# CPU_Power.net
KiCad netlist of a schematic drawn in Altium Designer
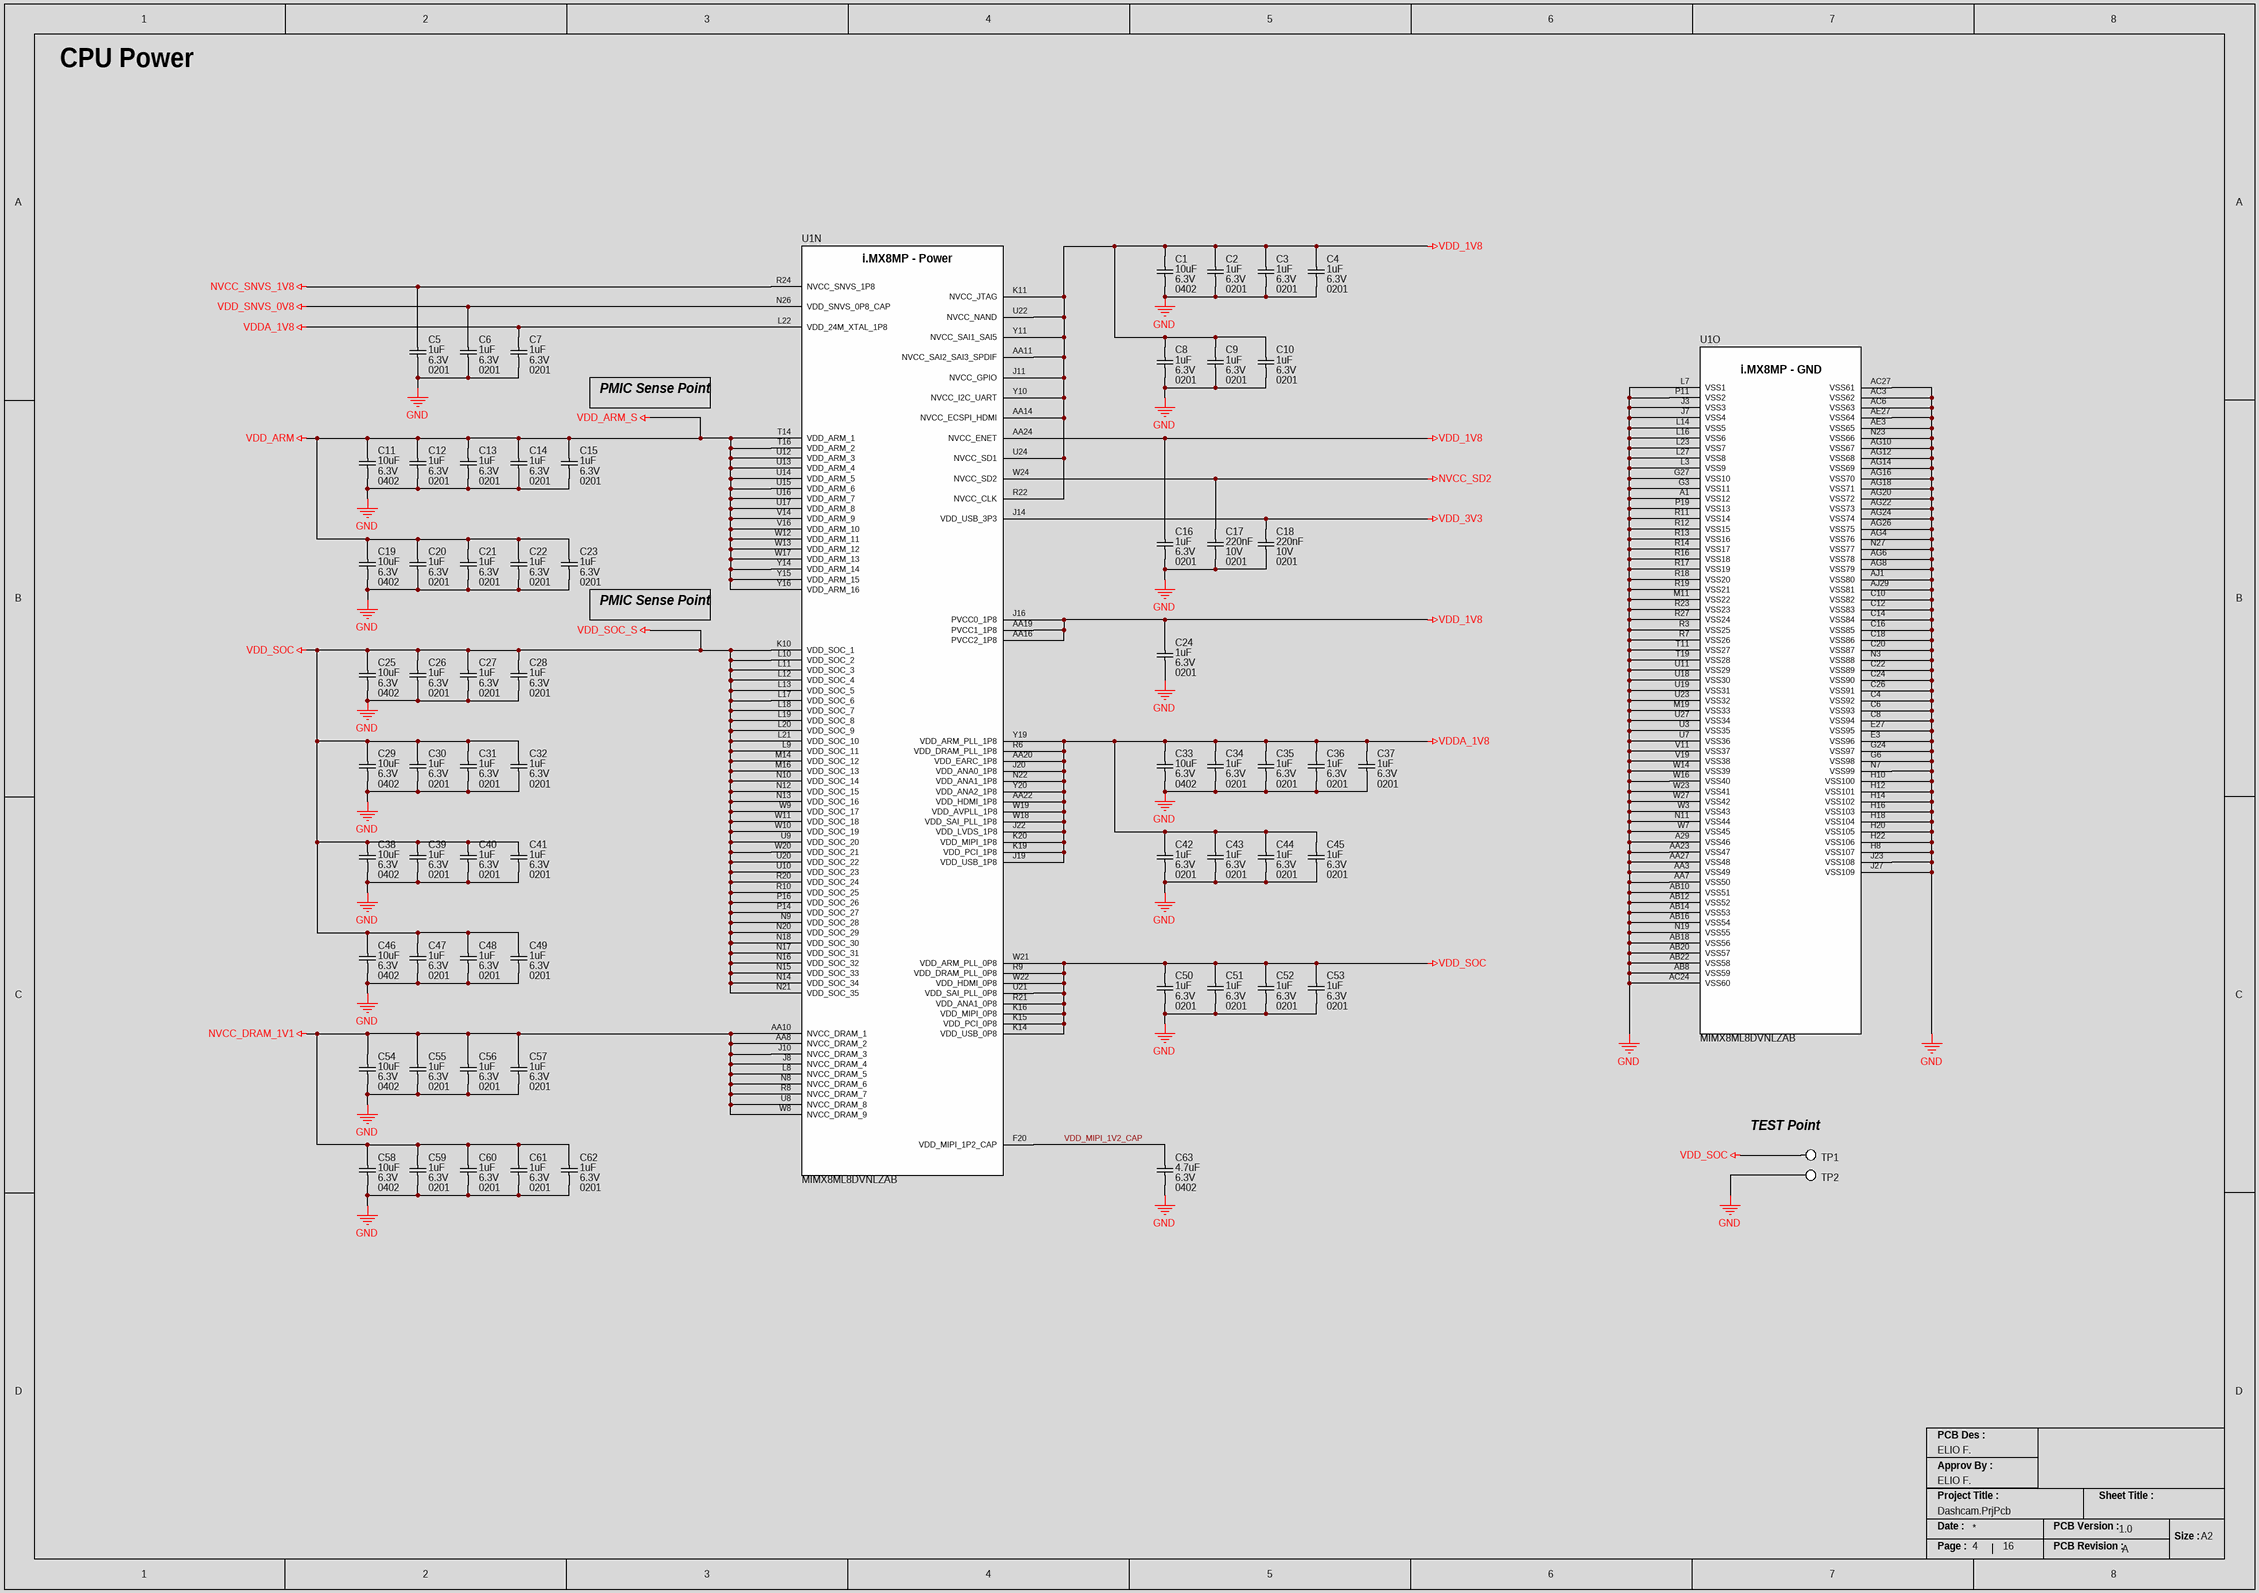
[diagram p0: CPU Power.SchDoc]

(export (version "E")
  (design (tool "Eeschema 10.0.6"))
  (components
    (comp (ref "C1")
      (value "CL05A106MQ5NUNC")
      (footprint "CAP_0402_CAPC1005X05N")
      (description "Cap Ceramic 10uF 6.3V X5R 20% SMD 0402 85C T/R")
      (fields
        (field (name "MANUFACTURER") "Samsung")
        (field (name "TOLERANCE") "20%")
        (field (name "CASE/PACKAGE") "0402")
        (field (name "CAPACITANCE") "10uF")
        (field (name "VOLTAGE RATING") "6.3V")
      )
      (libsource (lib "Electronic Devices_LIB") (part "CAP_10UF_6.3V_X5R_0402"))
    )
    (comp (ref "C2")
      (value "02016D105MAT2A")
      (footprint "CAP_0201_CAPC0603X03N")
      (description "0201 1 uF 6.3 V ±20 % Tolerance X5R Surface Mount Multilayer Ceramic Capacitor")
      (fields
        (field (name "MANUFACTURER") "Kyocera AVX")
        (field (name "TOLERANCE") "20%")
        (field (name "VOLTAGE RATING (DC)") "6.3V")
        (field (name "CAPACITANCE") "1uF")
        (field (name "CASE/PACKAGE") "0201")
      )
      (libsource (lib "Electronic Devices_LIB") (part "CAP_1UF_6.3V_X5R_0201"))
    )
    (comp (ref "C3")
      (value "02016D105MAT2A")
      (footprint "CAP_0201_CAPC0603X03N")
      (description "0201 1 uF 6.3 V ±20 % Tolerance X5R Surface Mount Multilayer Ceramic Capacitor")
      (fields
        (field (name "MANUFACTURER") "Kyocera AVX")
        (field (name "TOLERANCE") "20%")
        (field (name "VOLTAGE RATING (DC)") "6.3V")
        (field (name "CAPACITANCE") "1uF")
        (field (name "CASE/PACKAGE") "0201")
      )
      (libsource (lib "Electronic Devices_LIB") (part "CAP_1UF_6.3V_X5R_0201"))
    )
    (comp (ref "C4")
      (value "02016D105MAT2A")
      (footprint "CAP_0201_CAPC0603X03N")
      (description "0201 1 uF 6.3 V ±20 % Tolerance X5R Surface Mount Multilayer Ceramic Capacitor")
      (fields
        (field (name "MANUFACTURER") "Kyocera AVX")
        (field (name "TOLERANCE") "20%")
        (field (name "VOLTAGE RATING (DC)") "6.3V")
        (field (name "CAPACITANCE") "1uF")
        (field (name "CASE/PACKAGE") "0201")
      )
      (libsource (lib "Electronic Devices_LIB") (part "CAP_1UF_6.3V_X5R_0201"))
    )
    (comp (ref "C5")
      (value "02016D105MAT2A")
      (footprint "CAP_0201_CAPC0603X03N")
      (description "0201 1 uF 6.3 V ±20 % Tolerance X5R Surface Mount Multilayer Ceramic Capacitor")
      (fields
        (field (name "MANUFACTURER") "Kyocera AVX")
        (field (name "TOLERANCE") "20%")
        (field (name "VOLTAGE RATING (DC)") "6.3V")
        (field (name "CAPACITANCE") "1uF")
        (field (name "CASE/PACKAGE") "0201")
      )
      (libsource (lib "Electronic Devices_LIB") (part "CAP_1UF_6.3V_X5R_0201"))
    )
    (comp (ref "C6")
      (value "02016D105MAT2A")
      (footprint "CAP_0201_CAPC0603X03N")
      (description "0201 1 uF 6.3 V ±20 % Tolerance X5R Surface Mount Multilayer Ceramic Capacitor")
      (fields
        (field (name "MANUFACTURER") "Kyocera AVX")
        (field (name "TOLERANCE") "20%")
        (field (name "VOLTAGE RATING (DC)") "6.3V")
        (field (name "CAPACITANCE") "1uF")
        (field (name "CASE/PACKAGE") "0201")
      )
      (libsource (lib "Electronic Devices_LIB") (part "CAP_1UF_6.3V_X5R_0201"))
    )
    (comp (ref "C7")
      (value "02016D105MAT2A")
      (footprint "CAP_0201_CAPC0603X03N")
      (description "0201 1 uF 6.3 V ±20 % Tolerance X5R Surface Mount Multilayer Ceramic Capacitor")
      (fields
        (field (name "MANUFACTURER") "Kyocera AVX")
        (field (name "TOLERANCE") "20%")
        (field (name "VOLTAGE RATING (DC)") "6.3V")
        (field (name "CAPACITANCE") "1uF")
        (field (name "CASE/PACKAGE") "0201")
      )
      (libsource (lib "Electronic Devices_LIB") (part "CAP_1UF_6.3V_X5R_0201"))
    )
    (comp (ref "C8")
      (value "02016D105MAT2A")
      (footprint "CAP_0201_CAPC0603X03N")
      (description "0201 1 uF 6.3 V ±20 % Tolerance X5R Surface Mount Multilayer Ceramic Capacitor")
      (fields
        (field (name "MANUFACTURER") "Kyocera AVX")
        (field (name "TOLERANCE") "20%")
        (field (name "VOLTAGE RATING (DC)") "6.3V")
        (field (name "CAPACITANCE") "1uF")
        (field (name "CASE/PACKAGE") "0201")
      )
      (libsource (lib "Electronic Devices_LIB") (part "CAP_1UF_6.3V_X5R_0201"))
    )
    (comp (ref "C9")
      (value "02016D105MAT2A")
      (footprint "CAP_0201_CAPC0603X03N")
      (description "0201 1 uF 6.3 V ±20 % Tolerance X5R Surface Mount Multilayer Ceramic Capacitor")
      (fields
        (field (name "MANUFACTURER") "Kyocera AVX")
        (field (name "TOLERANCE") "20%")
        (field (name "VOLTAGE RATING (DC)") "6.3V")
        (field (name "CAPACITANCE") "1uF")
        (field (name "CASE/PACKAGE") "0201")
      )
      (libsource (lib "Electronic Devices_LIB") (part "CAP_1UF_6.3V_X5R_0201"))
    )
    (comp (ref "C10")
      (value "02016D105MAT2A")
      (footprint "CAP_0201_CAPC0603X03N")
      (description "0201 1 uF 6.3 V ±20 % Tolerance X5R Surface Mount Multilayer Ceramic Capacitor")
      (fields
        (field (name "MANUFACTURER") "Kyocera AVX")
        (field (name "TOLERANCE") "20%")
        (field (name "VOLTAGE RATING (DC)") "6.3V")
        (field (name "CAPACITANCE") "1uF")
        (field (name "CASE/PACKAGE") "0201")
      )
      (libsource (lib "Electronic Devices_LIB") (part "CAP_1UF_6.3V_X5R_0201"))
    )
    (comp (ref "C11")
      (value "CL05A106MQ5NUNC")
      (footprint "CAP_0402_CAPC1005X05N")
      (description "Cap Ceramic 10uF 6.3V X5R 20% SMD 0402 85C T/R")
      (fields
        (field (name "MANUFACTURER") "Samsung")
        (field (name "TOLERANCE") "20%")
        (field (name "CASE/PACKAGE") "0402")
        (field (name "CAPACITANCE") "10uF")
        (field (name "VOLTAGE RATING") "6.3V")
      )
      (libsource (lib "Electronic Devices_LIB") (part "CAP_10UF_6.3V_X5R_0402"))
    )
    (comp (ref "C12")
      (value "02016D105MAT2A")
      (footprint "CAP_0201_CAPC0603X03N")
      (description "0201 1 uF 6.3 V ±20 % Tolerance X5R Surface Mount Multilayer Ceramic Capacitor")
      (fields
        (field (name "MANUFACTURER") "Kyocera AVX")
        (field (name "TOLERANCE") "20%")
        (field (name "VOLTAGE RATING (DC)") "6.3V")
        (field (name "CAPACITANCE") "1uF")
        (field (name "CASE/PACKAGE") "0201")
      )
      (libsource (lib "Electronic Devices_LIB") (part "CAP_1UF_6.3V_X5R_0201"))
    )
    (comp (ref "C13")
      (value "02016D105MAT2A")
      (footprint "CAP_0201_CAPC0603X03N")
      (description "0201 1 uF 6.3 V ±20 % Tolerance X5R Surface Mount Multilayer Ceramic Capacitor")
      (fields
        (field (name "MANUFACTURER") "Kyocera AVX")
        (field (name "TOLERANCE") "20%")
        (field (name "VOLTAGE RATING (DC)") "6.3V")
        (field (name "CAPACITANCE") "1uF")
        (field (name "CASE/PACKAGE") "0201")
      )
      (libsource (lib "Electronic Devices_LIB") (part "CAP_1UF_6.3V_X5R_0201"))
    )
    (comp (ref "C14")
      (value "02016D105MAT2A")
      (footprint "CAP_0201_CAPC0603X03N")
      (description "0201 1 uF 6.3 V ±20 % Tolerance X5R Surface Mount Multilayer Ceramic Capacitor")
      (fields
        (field (name "MANUFACTURER") "Kyocera AVX")
        (field (name "TOLERANCE") "20%")
        (field (name "VOLTAGE RATING (DC)") "6.3V")
        (field (name "CAPACITANCE") "1uF")
        (field (name "CASE/PACKAGE") "0201")
      )
      (libsource (lib "Electronic Devices_LIB") (part "CAP_1UF_6.3V_X5R_0201"))
    )
    (comp (ref "C15")
      (value "02016D105MAT2A")
      (footprint "CAP_0201_CAPC0603X03N")
      (description "0201 1 uF 6.3 V ±20 % Tolerance X5R Surface Mount Multilayer Ceramic Capacitor")
      (fields
        (field (name "MANUFACTURER") "Kyocera AVX")
        (field (name "TOLERANCE") "20%")
        (field (name "VOLTAGE RATING (DC)") "6.3V")
        (field (name "CAPACITANCE") "1uF")
        (field (name "CASE/PACKAGE") "0201")
      )
      (libsource (lib "Electronic Devices_LIB") (part "CAP_1UF_6.3V_X5R_0201"))
    )
    (comp (ref "C16")
      (value "02016D105MAT2A")
      (footprint "CAP_0201_CAPC0603X03N")
      (description "0201 1 uF 6.3 V ±20 % Tolerance X5R Surface Mount Multilayer Ceramic Capacitor")
      (fields
        (field (name "MANUFACTURER") "Kyocera AVX")
        (field (name "TOLERANCE") "20%")
        (field (name "VOLTAGE RATING (DC)") "6.3V")
        (field (name "CAPACITANCE") "1uF")
        (field (name "CASE/PACKAGE") "0201")
      )
      (libsource (lib "Electronic Devices_LIB") (part "CAP_1UF_6.3V_X5R_0201"))
    )
    (comp (ref "C17")
      (value "LMK063BJ224MP-F")
      (footprint "CAP_0201_CAPC0603X03N")
      (description "Multilayer Ceramic Capacitors (High dielectric type), 10V, 0.22 uF, ± 20 %, 0201, X5R, RoHS")
      (fields
        (field (name "MANUFACTURER") "Taiyo Yuden")
        (field (name "TOLERANCE") "20%")
        (field (name "VOLTAGE RATING (DC)") "10V")
        (field (name "CAPACITANCE") "220nF")
        (field (name "CASE/PACKAGE") "0201")
      )
      (libsource (lib "Electronic Devices_LIB") (part "CAP_0.22UF_10V_X5R_0201"))
    )
    (comp (ref "C18")
      (value "LMK063BJ224MP-F")
      (footprint "CAP_0201_CAPC0603X03N")
      (description "Multilayer Ceramic Capacitors (High dielectric type), 10V, 0.22 uF, ± 20 %, 0201, X5R, RoHS")
      (fields
        (field (name "MANUFACTURER") "Taiyo Yuden")
        (field (name "TOLERANCE") "20%")
        (field (name "VOLTAGE RATING (DC)") "10V")
        (field (name "CAPACITANCE") "220nF")
        (field (name "CASE/PACKAGE") "0201")
      )
      (libsource (lib "Electronic Devices_LIB") (part "CAP_0.22UF_10V_X5R_0201"))
    )
    (comp (ref "C19")
      (value "CL05A106MQ5NUNC")
      (footprint "CAP_0402_CAPC1005X05N")
      (description "Cap Ceramic 10uF 6.3V X5R 20% SMD 0402 85C T/R")
      (fields
        (field (name "MANUFACTURER") "Samsung")
        (field (name "TOLERANCE") "20%")
        (field (name "CASE/PACKAGE") "0402")
        (field (name "CAPACITANCE") "10uF")
        (field (name "VOLTAGE RATING") "6.3V")
      )
      (libsource (lib "Electronic Devices_LIB") (part "CAP_10UF_6.3V_X5R_0402"))
    )
    (comp (ref "C20")
      (value "02016D105MAT2A")
      (footprint "CAP_0201_CAPC0603X03N")
      (description "0201 1 uF 6.3 V ±20 % Tolerance X5R Surface Mount Multilayer Ceramic Capacitor")
      (fields
        (field (name "MANUFACTURER") "Kyocera AVX")
        (field (name "TOLERANCE") "20%")
        (field (name "VOLTAGE RATING (DC)") "6.3V")
        (field (name "CAPACITANCE") "1uF")
        (field (name "CASE/PACKAGE") "0201")
      )
      (libsource (lib "Electronic Devices_LIB") (part "CAP_1UF_6.3V_X5R_0201"))
    )
    (comp (ref "C21")
      (value "02016D105MAT2A")
      (footprint "CAP_0201_CAPC0603X03N")
      (description "0201 1 uF 6.3 V ±20 % Tolerance X5R Surface Mount Multilayer Ceramic Capacitor")
      (fields
        (field (name "MANUFACTURER") "Kyocera AVX")
        (field (name "TOLERANCE") "20%")
        (field (name "VOLTAGE RATING (DC)") "6.3V")
        (field (name "CAPACITANCE") "1uF")
        (field (name "CASE/PACKAGE") "0201")
      )
      (libsource (lib "Electronic Devices_LIB") (part "CAP_1UF_6.3V_X5R_0201"))
    )
    (comp (ref "C22")
      (value "02016D105MAT2A")
      (footprint "CAP_0201_CAPC0603X03N")
      (description "0201 1 uF 6.3 V ±20 % Tolerance X5R Surface Mount Multilayer Ceramic Capacitor")
      (fields
        (field (name "MANUFACTURER") "Kyocera AVX")
        (field (name "TOLERANCE") "20%")
        (field (name "VOLTAGE RATING (DC)") "6.3V")
        (field (name "CAPACITANCE") "1uF")
        (field (name "CASE/PACKAGE") "0201")
      )
      (libsource (lib "Electronic Devices_LIB") (part "CAP_1UF_6.3V_X5R_0201"))
    )
    (comp (ref "C23")
      (value "02016D105MAT2A")
      (footprint "CAP_0201_CAPC0603X03N")
      (description "0201 1 uF 6.3 V ±20 % Tolerance X5R Surface Mount Multilayer Ceramic Capacitor")
      (fields
        (field (name "MANUFACTURER") "Kyocera AVX")
        (field (name "TOLERANCE") "20%")
        (field (name "VOLTAGE RATING (DC)") "6.3V")
        (field (name "CAPACITANCE") "1uF")
        (field (name "CASE/PACKAGE") "0201")
      )
      (libsource (lib "Electronic Devices_LIB") (part "CAP_1UF_6.3V_X5R_0201"))
    )
    (comp (ref "C24")
      (value "02016D105MAT2A")
      (footprint "CAP_0201_CAPC0603X03N")
      (description "0201 1 uF 6.3 V ±20 % Tolerance X5R Surface Mount Multilayer Ceramic Capacitor")
      (fields
        (field (name "MANUFACTURER") "Kyocera AVX")
        (field (name "TOLERANCE") "20%")
        (field (name "VOLTAGE RATING (DC)") "6.3V")
        (field (name "CAPACITANCE") "1uF")
        (field (name "CASE/PACKAGE") "0201")
      )
      (libsource (lib "Electronic Devices_LIB") (part "CAP_1UF_6.3V_X5R_0201"))
    )
    (comp (ref "C25")
      (value "CL05A106MQ5NUNC")
      (footprint "CAP_0402_CAPC1005X05N")
      (description "Cap Ceramic 10uF 6.3V X5R 20% SMD 0402 85C T/R")
      (fields
        (field (name "MANUFACTURER") "Samsung")
        (field (name "TOLERANCE") "20%")
        (field (name "CASE/PACKAGE") "0402")
        (field (name "CAPACITANCE") "10uF")
        (field (name "VOLTAGE RATING") "6.3V")
      )
      (libsource (lib "Electronic Devices_LIB") (part "CAP_10UF_6.3V_X5R_0402"))
    )
    (comp (ref "C26")
      (value "02016D105MAT2A")
      (footprint "CAP_0201_CAPC0603X03N")
      (description "0201 1 uF 6.3 V ±20 % Tolerance X5R Surface Mount Multilayer Ceramic Capacitor")
      (fields
        (field (name "MANUFACTURER") "Kyocera AVX")
        (field (name "TOLERANCE") "20%")
        (field (name "VOLTAGE RATING (DC)") "6.3V")
        (field (name "CAPACITANCE") "1uF")
        (field (name "CASE/PACKAGE") "0201")
      )
      (libsource (lib "Electronic Devices_LIB") (part "CAP_1UF_6.3V_X5R_0201"))
    )
    (comp (ref "C27")
      (value "02016D105MAT2A")
      (footprint "CAP_0201_CAPC0603X03N")
      (description "0201 1 uF 6.3 V ±20 % Tolerance X5R Surface Mount Multilayer Ceramic Capacitor")
      (fields
        (field (name "MANUFACTURER") "Kyocera AVX")
        (field (name "TOLERANCE") "20%")
        (field (name "VOLTAGE RATING (DC)") "6.3V")
        (field (name "CAPACITANCE") "1uF")
        (field (name "CASE/PACKAGE") "0201")
      )
      (libsource (lib "Electronic Devices_LIB") (part "CAP_1UF_6.3V_X5R_0201"))
    )
    (comp (ref "C28")
      (value "02016D105MAT2A")
      (footprint "CAP_0201_CAPC0603X03N")
      (description "0201 1 uF 6.3 V ±20 % Tolerance X5R Surface Mount Multilayer Ceramic Capacitor")
      (fields
        (field (name "MANUFACTURER") "Kyocera AVX")
        (field (name "TOLERANCE") "20%")
        (field (name "VOLTAGE RATING (DC)") "6.3V")
        (field (name "CAPACITANCE") "1uF")
        (field (name "CASE/PACKAGE") "0201")
      )
      (libsource (lib "Electronic Devices_LIB") (part "CAP_1UF_6.3V_X5R_0201"))
    )
    (comp (ref "C29")
      (value "CL05A106MQ5NUNC")
      (footprint "CAP_0402_CAPC1005X05N")
      (description "Cap Ceramic 10uF 6.3V X5R 20% SMD 0402 85C T/R")
      (fields
        (field (name "MANUFACTURER") "Samsung")
        (field (name "TOLERANCE") "20%")
        (field (name "CASE/PACKAGE") "0402")
        (field (name "CAPACITANCE") "10uF")
        (field (name "VOLTAGE RATING") "6.3V")
      )
      (libsource (lib "Electronic Devices_LIB") (part "CAP_10UF_6.3V_X5R_0402"))
    )
    (comp (ref "C30")
      (value "02016D105MAT2A")
      (footprint "CAP_0201_CAPC0603X03N")
      (description "0201 1 uF 6.3 V ±20 % Tolerance X5R Surface Mount Multilayer Ceramic Capacitor")
      (fields
        (field (name "MANUFACTURER") "Kyocera AVX")
        (field (name "TOLERANCE") "20%")
        (field (name "VOLTAGE RATING (DC)") "6.3V")
        (field (name "CAPACITANCE") "1uF")
        (field (name "CASE/PACKAGE") "0201")
      )
      (libsource (lib "Electronic Devices_LIB") (part "CAP_1UF_6.3V_X5R_0201"))
    )
    (comp (ref "C31")
      (value "02016D105MAT2A")
      (footprint "CAP_0201_CAPC0603X03N")
      (description "0201 1 uF 6.3 V ±20 % Tolerance X5R Surface Mount Multilayer Ceramic Capacitor")
      (fields
        (field (name "MANUFACTURER") "Kyocera AVX")
        (field (name "TOLERANCE") "20%")
        (field (name "VOLTAGE RATING (DC)") "6.3V")
        (field (name "CAPACITANCE") "1uF")
        (field (name "CASE/PACKAGE") "0201")
      )
      (libsource (lib "Electronic Devices_LIB") (part "CAP_1UF_6.3V_X5R_0201"))
    )
    (comp (ref "C32")
      (value "02016D105MAT2A")
      (footprint "CAP_0201_CAPC0603X03N")
      (description "0201 1 uF 6.3 V ±20 % Tolerance X5R Surface Mount Multilayer Ceramic Capacitor")
      (fields
        (field (name "MANUFACTURER") "Kyocera AVX")
        (field (name "TOLERANCE") "20%")
        (field (name "VOLTAGE RATING (DC)") "6.3V")
        (field (name "CAPACITANCE") "1uF")
        (field (name "CASE/PACKAGE") "0201")
      )
      (libsource (lib "Electronic Devices_LIB") (part "CAP_1UF_6.3V_X5R_0201"))
    )
    (comp (ref "C33")
      (value "CL05A106MQ5NUNC")
      (footprint "CAP_0402_CAPC1005X05N")
      (description "Cap Ceramic 10uF 6.3V X5R 20% SMD 0402 85C T/R")
      (fields
        (field (name "MANUFACTURER") "Samsung")
        (field (name "TOLERANCE") "20%")
        (field (name "CASE/PACKAGE") "0402")
        (field (name "CAPACITANCE") "10uF")
        (field (name "VOLTAGE RATING") "6.3V")
      )
      (libsource (lib "Electronic Devices_LIB") (part "CAP_10UF_6.3V_X5R_0402"))
    )
    (comp (ref "C34")
      (value "02016D105MAT2A")
      (footprint "CAP_0201_CAPC0603X03N")
      (description "0201 1 uF 6.3 V ±20 % Tolerance X5R Surface Mount Multilayer Ceramic Capacitor")
      (fields
        (field (name "MANUFACTURER") "Kyocera AVX")
        (field (name "TOLERANCE") "20%")
        (field (name "VOLTAGE RATING (DC)") "6.3V")
        (field (name "CAPACITANCE") "1uF")
        (field (name "CASE/PACKAGE") "0201")
      )
      (libsource (lib "Electronic Devices_LIB") (part "CAP_1UF_6.3V_X5R_0201"))
    )
    (comp (ref "C35")
      (value "02016D105MAT2A")
      (footprint "CAP_0201_CAPC0603X03N")
      (description "0201 1 uF 6.3 V ±20 % Tolerance X5R Surface Mount Multilayer Ceramic Capacitor")
      (fields
        (field (name "MANUFACTURER") "Kyocera AVX")
        (field (name "TOLERANCE") "20%")
        (field (name "VOLTAGE RATING (DC)") "6.3V")
        (field (name "CAPACITANCE") "1uF")
        (field (name "CASE/PACKAGE") "0201")
      )
      (libsource (lib "Electronic Devices_LIB") (part "CAP_1UF_6.3V_X5R_0201"))
    )
    (comp (ref "C36")
      (value "02016D105MAT2A")
      (footprint "CAP_0201_CAPC0603X03N")
      (description "0201 1 uF 6.3 V ±20 % Tolerance X5R Surface Mount Multilayer Ceramic Capacitor")
      (fields
        (field (name "MANUFACTURER") "Kyocera AVX")
        (field (name "TOLERANCE") "20%")
        (field (name "VOLTAGE RATING (DC)") "6.3V")
        (field (name "CAPACITANCE") "1uF")
        (field (name "CASE/PACKAGE") "0201")
      )
      (libsource (lib "Electronic Devices_LIB") (part "CAP_1UF_6.3V_X5R_0201"))
    )
    (comp (ref "C37")
      (value "02016D105MAT2A")
      (footprint "CAP_0201_CAPC0603X03N")
      (description "0201 1 uF 6.3 V ±20 % Tolerance X5R Surface Mount Multilayer Ceramic Capacitor")
      (fields
        (field (name "MANUFACTURER") "Kyocera AVX")
        (field (name "TOLERANCE") "20%")
        (field (name "VOLTAGE RATING (DC)") "6.3V")
        (field (name "CAPACITANCE") "1uF")
        (field (name "CASE/PACKAGE") "0201")
      )
      (libsource (lib "Electronic Devices_LIB") (part "CAP_1UF_6.3V_X5R_0201"))
    )
    (comp (ref "C38")
      (value "CL05A106MQ5NUNC")
      (footprint "CAP_0402_CAPC1005X05N")
      (description "Cap Ceramic 10uF 6.3V X5R 20% SMD 0402 85C T/R")
      (fields
        (field (name "MANUFACTURER") "Samsung")
        (field (name "TOLERANCE") "20%")
        (field (name "CASE/PACKAGE") "0402")
        (field (name "CAPACITANCE") "10uF")
        (field (name "VOLTAGE RATING") "6.3V")
      )
      (libsource (lib "Electronic Devices_LIB") (part "CAP_10UF_6.3V_X5R_0402"))
    )
    (comp (ref "C39")
      (value "02016D105MAT2A")
      (footprint "CAP_0201_CAPC0603X03N")
      (description "0201 1 uF 6.3 V ±20 % Tolerance X5R Surface Mount Multilayer Ceramic Capacitor")
      (fields
        (field (name "MANUFACTURER") "Kyocera AVX")
        (field (name "TOLERANCE") "20%")
        (field (name "VOLTAGE RATING (DC)") "6.3V")
        (field (name "CAPACITANCE") "1uF")
        (field (name "CASE/PACKAGE") "0201")
      )
      (libsource (lib "Electronic Devices_LIB") (part "CAP_1UF_6.3V_X5R_0201"))
    )
    (comp (ref "C40")
      (value "02016D105MAT2A")
      (footprint "CAP_0201_CAPC0603X03N")
      (description "0201 1 uF 6.3 V ±20 % Tolerance X5R Surface Mount Multilayer Ceramic Capacitor")
      (fields
        (field (name "MANUFACTURER") "Kyocera AVX")
        (field (name "TOLERANCE") "20%")
        (field (name "VOLTAGE RATING (DC)") "6.3V")
        (field (name "CAPACITANCE") "1uF")
        (field (name "CASE/PACKAGE") "0201")
      )
      (libsource (lib "Electronic Devices_LIB") (part "CAP_1UF_6.3V_X5R_0201"))
    )
    (comp (ref "C41")
      (value "02016D105MAT2A")
      (footprint "CAP_0201_CAPC0603X03N")
      (description "0201 1 uF 6.3 V ±20 % Tolerance X5R Surface Mount Multilayer Ceramic Capacitor")
      (fields
        (field (name "MANUFACTURER") "Kyocera AVX")
        (field (name "TOLERANCE") "20%")
        (field (name "VOLTAGE RATING (DC)") "6.3V")
        (field (name "CAPACITANCE") "1uF")
        (field (name "CASE/PACKAGE") "0201")
      )
      (libsource (lib "Electronic Devices_LIB") (part "CAP_1UF_6.3V_X5R_0201"))
    )
    (comp (ref "C42")
      (value "02016D105MAT2A")
      (footprint "CAP_0201_CAPC0603X03N")
      (description "0201 1 uF 6.3 V ±20 % Tolerance X5R Surface Mount Multilayer Ceramic Capacitor")
      (fields
        (field (name "MANUFACTURER") "Kyocera AVX")
        (field (name "TOLERANCE") "20%")
        (field (name "VOLTAGE RATING (DC)") "6.3V")
        (field (name "CAPACITANCE") "1uF")
        (field (name "CASE/PACKAGE") "0201")
      )
      (libsource (lib "Electronic Devices_LIB") (part "CAP_1UF_6.3V_X5R_0201"))
    )
    (comp (ref "C43")
      (value "02016D105MAT2A")
      (footprint "CAP_0201_CAPC0603X03N")
      (description "0201 1 uF 6.3 V ±20 % Tolerance X5R Surface Mount Multilayer Ceramic Capacitor")
      (fields
        (field (name "MANUFACTURER") "Kyocera AVX")
        (field (name "TOLERANCE") "20%")
        (field (name "VOLTAGE RATING (DC)") "6.3V")
        (field (name "CAPACITANCE") "1uF")
        (field (name "CASE/PACKAGE") "0201")
      )
      (libsource (lib "Electronic Devices_LIB") (part "CAP_1UF_6.3V_X5R_0201"))
    )
    (comp (ref "C44")
      (value "02016D105MAT2A")
      (footprint "CAP_0201_CAPC0603X03N")
      (description "0201 1 uF 6.3 V ±20 % Tolerance X5R Surface Mount Multilayer Ceramic Capacitor")
      (fields
        (field (name "MANUFACTURER") "Kyocera AVX")
        (field (name "TOLERANCE") "20%")
        (field (name "VOLTAGE RATING (DC)") "6.3V")
        (field (name "CAPACITANCE") "1uF")
        (field (name "CASE/PACKAGE") "0201")
      )
      (libsource (lib "Electronic Devices_LIB") (part "CAP_1UF_6.3V_X5R_0201"))
    )
    (comp (ref "C45")
      (value "02016D105MAT2A")
      (footprint "CAP_0201_CAPC0603X03N")
      (description "0201 1 uF 6.3 V ±20 % Tolerance X5R Surface Mount Multilayer Ceramic Capacitor")
      (fields
        (field (name "MANUFACTURER") "Kyocera AVX")
        (field (name "TOLERANCE") "20%")
        (field (name "VOLTAGE RATING (DC)") "6.3V")
        (field (name "CAPACITANCE") "1uF")
        (field (name "CASE/PACKAGE") "0201")
      )
      (libsource (lib "Electronic Devices_LIB") (part "CAP_1UF_6.3V_X5R_0201"))
    )
    (comp (ref "C46")
      (value "CL05A106MQ5NUNC")
      (footprint "CAP_0402_CAPC1005X05N")
      (description "Cap Ceramic 10uF 6.3V X5R 20% SMD 0402 85C T/R")
      (fields
        (field (name "MANUFACTURER") "Samsung")
        (field (name "TOLERANCE") "20%")
        (field (name "CASE/PACKAGE") "0402")
        (field (name "CAPACITANCE") "10uF")
        (field (name "VOLTAGE RATING") "6.3V")
      )
      (libsource (lib "Electronic Devices_LIB") (part "CAP_10UF_6.3V_X5R_0402"))
    )
    (comp (ref "C47")
      (value "02016D105MAT2A")
      (footprint "CAP_0201_CAPC0603X03N")
      (description "0201 1 uF 6.3 V ±20 % Tolerance X5R Surface Mount Multilayer Ceramic Capacitor")
      (fields
        (field (name "MANUFACTURER") "Kyocera AVX")
        (field (name "TOLERANCE") "20%")
        (field (name "VOLTAGE RATING (DC)") "6.3V")
        (field (name "CAPACITANCE") "1uF")
        (field (name "CASE/PACKAGE") "0201")
      )
      (libsource (lib "Electronic Devices_LIB") (part "CAP_1UF_6.3V_X5R_0201"))
    )
    (comp (ref "C48")
      (value "02016D105MAT2A")
      (footprint "CAP_0201_CAPC0603X03N")
      (description "0201 1 uF 6.3 V ±20 % Tolerance X5R Surface Mount Multilayer Ceramic Capacitor")
      (fields
        (field (name "MANUFACTURER") "Kyocera AVX")
        (field (name "TOLERANCE") "20%")
        (field (name "VOLTAGE RATING (DC)") "6.3V")
        (field (name "CAPACITANCE") "1uF")
        (field (name "CASE/PACKAGE") "0201")
      )
      (libsource (lib "Electronic Devices_LIB") (part "CAP_1UF_6.3V_X5R_0201"))
    )
    (comp (ref "C49")
      (value "02016D105MAT2A")
      (footprint "CAP_0201_CAPC0603X03N")
      (description "0201 1 uF 6.3 V ±20 % Tolerance X5R Surface Mount Multilayer Ceramic Capacitor")
      (fields
        (field (name "MANUFACTURER") "Kyocera AVX")
        (field (name "TOLERANCE") "20%")
        (field (name "VOLTAGE RATING (DC)") "6.3V")
        (field (name "CAPACITANCE") "1uF")
        (field (name "CASE/PACKAGE") "0201")
      )
      (libsource (lib "Electronic Devices_LIB") (part "CAP_1UF_6.3V_X5R_0201"))
    )
    (comp (ref "C50")
      (value "02016D105MAT2A")
      (footprint "CAP_0201_CAPC0603X03N")
      (description "0201 1 uF 6.3 V ±20 % Tolerance X5R Surface Mount Multilayer Ceramic Capacitor")
      (fields
        (field (name "MANUFACTURER") "Kyocera AVX")
        (field (name "TOLERANCE") "20%")
        (field (name "VOLTAGE RATING (DC)") "6.3V")
        (field (name "CAPACITANCE") "1uF")
        (field (name "CASE/PACKAGE") "0201")
      )
      (libsource (lib "Electronic Devices_LIB") (part "CAP_1UF_6.3V_X5R_0201"))
    )
    (comp (ref "C51")
      (value "02016D105MAT2A")
      (footprint "CAP_0201_CAPC0603X03N")
      (description "0201 1 uF 6.3 V ±20 % Tolerance X5R Surface Mount Multilayer Ceramic Capacitor")
      (fields
        (field (name "MANUFACTURER") "Kyocera AVX")
        (field (name "TOLERANCE") "20%")
        (field (name "VOLTAGE RATING (DC)") "6.3V")
        (field (name "CAPACITANCE") "1uF")
        (field (name "CASE/PACKAGE") "0201")
      )
      (libsource (lib "Electronic Devices_LIB") (part "CAP_1UF_6.3V_X5R_0201"))
    )
    (comp (ref "C52")
      (value "02016D105MAT2A")
      (footprint "CAP_0201_CAPC0603X03N")
      (description "0201 1 uF 6.3 V ±20 % Tolerance X5R Surface Mount Multilayer Ceramic Capacitor")
      (fields
        (field (name "MANUFACTURER") "Kyocera AVX")
        (field (name "TOLERANCE") "20%")
        (field (name "VOLTAGE RATING (DC)") "6.3V")
        (field (name "CAPACITANCE") "1uF")
        (field (name "CASE/PACKAGE") "0201")
      )
      (libsource (lib "Electronic Devices_LIB") (part "CAP_1UF_6.3V_X5R_0201"))
    )
    (comp (ref "C53")
      (value "02016D105MAT2A")
      (footprint "CAP_0201_CAPC0603X03N")
      (description "0201 1 uF 6.3 V ±20 % Tolerance X5R Surface Mount Multilayer Ceramic Capacitor")
      (fields
        (field (name "MANUFACTURER") "Kyocera AVX")
        (field (name "TOLERANCE") "20%")
        (field (name "VOLTAGE RATING (DC)") "6.3V")
        (field (name "CAPACITANCE") "1uF")
        (field (name "CASE/PACKAGE") "0201")
      )
      (libsource (lib "Electronic Devices_LIB") (part "CAP_1UF_6.3V_X5R_0201"))
    )
    (comp (ref "C54")
      (value "CL05A106MQ5NUNC")
      (footprint "CAP_0402_CAPC1005X05N")
      (description "Cap Ceramic 10uF 6.3V X5R 20% SMD 0402 85C T/R")
      (fields
        (field (name "MANUFACTURER") "Samsung")
        (field (name "TOLERANCE") "20%")
        (field (name "CASE/PACKAGE") "0402")
        (field (name "CAPACITANCE") "10uF")
        (field (name "VOLTAGE RATING") "6.3V")
      )
      (libsource (lib "Electronic Devices_LIB") (part "CAP_10UF_6.3V_X5R_0402"))
    )
    (comp (ref "C55")
      (value "02016D105MAT2A")
      (footprint "CAP_0201_CAPC0603X03N")
      (description "0201 1 uF 6.3 V ±20 % Tolerance X5R Surface Mount Multilayer Ceramic Capacitor")
      (fields
        (field (name "MANUFACTURER") "Kyocera AVX")
        (field (name "TOLERANCE") "20%")
        (field (name "VOLTAGE RATING (DC)") "6.3V")
        (field (name "CAPACITANCE") "1uF")
        (field (name "CASE/PACKAGE") "0201")
      )
      (libsource (lib "Electronic Devices_LIB") (part "CAP_1UF_6.3V_X5R_0201"))
    )
    (comp (ref "C56")
      (value "02016D105MAT2A")
      (footprint "CAP_0201_CAPC0603X03N")
      (description "0201 1 uF 6.3 V ±20 % Tolerance X5R Surface Mount Multilayer Ceramic Capacitor")
      (fields
        (field (name "MANUFACTURER") "Kyocera AVX")
        (field (name "TOLERANCE") "20%")
        (field (name "VOLTAGE RATING (DC)") "6.3V")
        (field (name "CAPACITANCE") "1uF")
        (field (name "CASE/PACKAGE") "0201")
      )
      (libsource (lib "Electronic Devices_LIB") (part "CAP_1UF_6.3V_X5R_0201"))
    )
    (comp (ref "C57")
      (value "02016D105MAT2A")
      (footprint "CAP_0201_CAPC0603X03N")
      (description "0201 1 uF 6.3 V ±20 % Tolerance X5R Surface Mount Multilayer Ceramic Capacitor")
      (fields
        (field (name "MANUFACTURER") "Kyocera AVX")
        (field (name "TOLERANCE") "20%")
        (field (name "VOLTAGE RATING (DC)") "6.3V")
        (field (name "CAPACITANCE") "1uF")
        (field (name "CASE/PACKAGE") "0201")
      )
      (libsource (lib "Electronic Devices_LIB") (part "CAP_1UF_6.3V_X5R_0201"))
    )
    (comp (ref "C58")
      (value "CL05A106MQ5NUNC")
      (footprint "CAP_0402_CAPC1005X05N")
      (description "Cap Ceramic 10uF 6.3V X5R 20% SMD 0402 85C T/R")
      (fields
        (field (name "MANUFACTURER") "Samsung")
        (field (name "TOLERANCE") "20%")
        (field (name "CASE/PACKAGE") "0402")
        (field (name "CAPACITANCE") "10uF")
        (field (name "VOLTAGE RATING") "6.3V")
      )
      (libsource (lib "Electronic Devices_LIB") (part "CAP_10UF_6.3V_X5R_0402"))
    )
    (comp (ref "C59")
      (value "02016D105MAT2A")
      (footprint "CAP_0201_CAPC0603X03N")
      (description "0201 1 uF 6.3 V ±20 % Tolerance X5R Surface Mount Multilayer Ceramic Capacitor")
      (fields
        (field (name "MANUFACTURER") "Kyocera AVX")
        (field (name "TOLERANCE") "20%")
        (field (name "VOLTAGE RATING (DC)") "6.3V")
        (field (name "CAPACITANCE") "1uF")
        (field (name "CASE/PACKAGE") "0201")
      )
      (libsource (lib "Electronic Devices_LIB") (part "CAP_1UF_6.3V_X5R_0201"))
    )
    (comp (ref "C60")
      (value "02016D105MAT2A")
      (footprint "CAP_0201_CAPC0603X03N")
      (description "0201 1 uF 6.3 V ±20 % Tolerance X5R Surface Mount Multilayer Ceramic Capacitor")
      (fields
        (field (name "MANUFACTURER") "Kyocera AVX")
        (field (name "TOLERANCE") "20%")
        (field (name "VOLTAGE RATING (DC)") "6.3V")
        (field (name "CAPACITANCE") "1uF")
        (field (name "CASE/PACKAGE") "0201")
      )
      (libsource (lib "Electronic Devices_LIB") (part "CAP_1UF_6.3V_X5R_0201"))
    )
    (comp (ref "C61")
      (value "02016D105MAT2A")
      (footprint "CAP_0201_CAPC0603X03N")
      (description "0201 1 uF 6.3 V ±20 % Tolerance X5R Surface Mount Multilayer Ceramic Capacitor")
      (fields
        (field (name "MANUFACTURER") "Kyocera AVX")
        (field (name "TOLERANCE") "20%")
        (field (name "VOLTAGE RATING (DC)") "6.3V")
        (field (name "CAPACITANCE") "1uF")
        (field (name "CASE/PACKAGE") "0201")
      )
      (libsource (lib "Electronic Devices_LIB") (part "CAP_1UF_6.3V_X5R_0201"))
    )
    (comp (ref "C62")
      (value "02016D105MAT2A")
      (footprint "CAP_0201_CAPC0603X03N")
      (description "0201 1 uF 6.3 V ±20 % Tolerance X5R Surface Mount Multilayer Ceramic Capacitor")
      (fields
        (field (name "MANUFACTURER") "Kyocera AVX")
        (field (name "TOLERANCE") "20%")
        (field (name "VOLTAGE RATING (DC)") "6.3V")
        (field (name "CAPACITANCE") "1uF")
        (field (name "CASE/PACKAGE") "0201")
      )
      (libsource (lib "Electronic Devices_LIB") (part "CAP_1UF_6.3V_X5R_0201"))
    )
    (comp (ref "C63")
      (value "C1005X5R0J475M050BC")
      (footprint "CAP_0402_CAPC1005X05N")
      (description "Multilayer Ceramic Capacitor, 4.7 uF, 6.3 V, ± 20%, X5R, 0402 [1005 Metric]")
      (fields
        (field (name "MANUFACTURER") "TDK")
        (field (name "TOLERANCE") "20%")
        (field (name "CAPACITANCE") "4.7uF")
        (field (name "VOLTAGE RATING") "6.3V")
        (field (name "CASE/PACKAGE") "0402")
      )
      (libsource (lib "Electronic Devices_LIB") (part "CAP_4.7UF_6.3V_X5R_0402"))
    )
    (comp (ref "TP1")
      (value "NO COMPONENT")
      (footprint "TP_PAD_0.8MM_SMD_ROUND")
      (description "Test Point, SMD pad, round, 1.5mm, 1.6mm, 3mm diameter")
      (libsource (lib "Electronic Devices_LIB") (part "TP_PAD_SMD_Round"))
    )
    (comp (ref "TP2")
      (value "NO COMPONENT")
      (footprint "TP_PAD_0.8MM_SMD_ROUND")
      (description "Test Point, SMD pad, round, 1.5mm, 1.6mm, 3mm diameter")
      (libsource (lib "Electronic Devices_LIB") (part "TP_PAD_SMD_Round"))
    )
    (comp (ref "U1")
      (value "MIMX8ML8DVNLZAB")
      (footprint "IC_MPU_BGA548C50P29X29_1500X1500X148")
      (description "i.MX 8M Plus, Consumer, / TRAY TRAY MULTIPLE DP BAKEABLE RoHS Compliant: Yes")
      (fields (field (name "MANUFACTURER") "NXP Semiconductors"))
      (libsource (lib "Electronic Devices_LIB") (part "IC_MPU_8M_PLUS_MIMX8ML8DVNLZAB"))
    )
  )
  (nets
    (net (code "1") (name "/VDD_MIPI_1V2_CAP") (class "Default")
      (node (ref "C63") (pin "2") (pinfunction "2_2") (pintype "passive"))
      (node (ref "U1") (pin "F20") (pinfunction "VDD_MIPI_1P2_CAP_F20") (pintype "power_in"))
    )
    (net (code "2") (name "GND") (class "Default")
      (node (ref "C1") (pin "1") (pinfunction "1_1") (pintype "passive"))
      (node (ref "C10") (pin "1") (pinfunction "1_1") (pintype "passive"))
      (node (ref "C11") (pin "1") (pinfunction "1_1") (pintype "passive"))
      (node (ref "C12") (pin "1") (pinfunction "1_1") (pintype "passive"))
      (node (ref "C13") (pin "1") (pinfunction "1_1") (pintype "passive"))
      (node (ref "C14") (pin "1") (pinfunction "1_1") (pintype "passive"))
      (node (ref "C15") (pin "1") (pinfunction "1_1") (pintype "passive"))
      (node (ref "C16") (pin "1") (pinfunction "1_1") (pintype "passive"))
      (node (ref "C17") (pin "1") (pinfunction "1_1") (pintype "passive"))
      (node (ref "C18") (pin "1") (pinfunction "1_1") (pintype "passive"))
      (node (ref "C19") (pin "1") (pinfunction "1_1") (pintype "passive"))
      (node (ref "C2") (pin "1") (pinfunction "1_1") (pintype "passive"))
      (node (ref "C20") (pin "1") (pinfunction "1_1") (pintype "passive"))
      (node (ref "C21") (pin "1") (pinfunction "1_1") (pintype "passive"))
      (node (ref "C22") (pin "1") (pinfunction "1_1") (pintype "passive"))
      (node (ref "C23") (pin "1") (pinfunction "1_1") (pintype "passive"))
      (node (ref "C24") (pin "1") (pinfunction "1_1") (pintype "passive"))
      (node (ref "C25") (pin "1") (pinfunction "1_1") (pintype "passive"))
      (node (ref "C26") (pin "1") (pinfunction "1_1") (pintype "passive"))
      (node (ref "C27") (pin "1") (pinfunction "1_1") (pintype "passive"))
      (node (ref "C28") (pin "1") (pinfunction "1_1") (pintype "passive"))
      (node (ref "C29") (pin "1") (pinfunction "1_1") (pintype "passive"))
      (node (ref "C3") (pin "1") (pinfunction "1_1") (pintype "passive"))
      (node (ref "C30") (pin "1") (pinfunction "1_1") (pintype "passive"))
      (node (ref "C31") (pin "1") (pinfunction "1_1") (pintype "passive"))
      (node (ref "C32") (pin "1") (pinfunction "1_1") (pintype "passive"))
      (node (ref "C33") (pin "1") (pinfunction "1_1") (pintype "passive"))
      (node (ref "C34") (pin "1") (pinfunction "1_1") (pintype "passive"))
      (node (ref "C35") (pin "1") (pinfunction "1_1") (pintype "passive"))
      (node (ref "C36") (pin "1") (pinfunction "1_1") (pintype "passive"))
      (node (ref "C37") (pin "1") (pinfunction "1_1") (pintype "passive"))
      (node (ref "C38") (pin "1") (pinfunction "1_1") (pintype "passive"))
      (node (ref "C39") (pin "1") (pinfunction "1_1") (pintype "passive"))
      (node (ref "C4") (pin "1") (pinfunction "1_1") (pintype "passive"))
      (node (ref "C40") (pin "1") (pinfunction "1_1") (pintype "passive"))
      (node (ref "C41") (pin "1") (pinfunction "1_1") (pintype "passive"))
      (node (ref "C42") (pin "1") (pinfunction "1_1") (pintype "passive"))
      (node (ref "C43") (pin "1") (pinfunction "1_1") (pintype "passive"))
      (node (ref "C44") (pin "1") (pinfunction "1_1") (pintype "passive"))
      (node (ref "C45") (pin "1") (pinfunction "1_1") (pintype "passive"))
      (node (ref "C46") (pin "1") (pinfunction "1_1") (pintype "passive"))
      (node (ref "C47") (pin "1") (pinfunction "1_1") (pintype "passive"))
      (node (ref "C48") (pin "1") (pinfunction "1_1") (pintype "passive"))
      (node (ref "C49") (pin "1") (pinfunction "1_1") (pintype "passive"))
      (node (ref "C5") (pin "1") (pinfunction "1_1") (pintype "passive"))
      (node (ref "C50") (pin "1") (pinfunction "1_1") (pintype "passive"))
      (node (ref "C51") (pin "1") (pinfunction "1_1") (pintype "passive"))
      (node (ref "C52") (pin "1") (pinfunction "1_1") (pintype "passive"))
      (node (ref "C53") (pin "1") (pinfunction "1_1") (pintype "passive"))
      (node (ref "C54") (pin "1") (pinfunction "1_1") (pintype "passive"))
      (node (ref "C55") (pin "1") (pinfunction "1_1") (pintype "passive"))
      (node (ref "C56") (pin "1") (pinfunction "1_1") (pintype "passive"))
      (node (ref "C57") (pin "1") (pinfunction "1_1") (pintype "passive"))
      (node (ref "C58") (pin "1") (pinfunction "1_1") (pintype "passive"))
      (node (ref "C59") (pin "1") (pinfunction "1_1") (pintype "passive"))
      (node (ref "C6") (pin "1") (pinfunction "1_1") (pintype "passive"))
      (node (ref "C60") (pin "1") (pinfunction "1_1") (pintype "passive"))
      (node (ref "C61") (pin "1") (pinfunction "1_1") (pintype "passive"))
      (node (ref "C62") (pin "1") (pinfunction "1_1") (pintype "passive"))
      (node (ref "C63") (pin "1") (pinfunction "1_1") (pintype "passive"))
      (node (ref "C7") (pin "1") (pinfunction "1_1") (pintype "passive"))
      (node (ref "C8") (pin "1") (pinfunction "1_1") (pintype "passive"))
      (node (ref "C9") (pin "1") (pinfunction "1_1") (pintype "passive"))
      (node (ref "TP2") (pin "1") (pinfunction "1_1") (pintype "passive"))
      (node (ref "U1") (pin "A1") (pinfunction "VSS12_A1") (pintype "power_in"))
      (node (ref "U1") (pin "A29") (pinfunction "VSS46_A29") (pintype "power_in"))
      (node (ref "U1") (pin "AA23") (pinfunction "VSS47_AA23") (pintype "power_in"))
      (node (ref "U1") (pin "AA27") (pinfunction "VSS48_AA27") (pintype "power_in"))
      (node (ref "U1") (pin "AA3") (pinfunction "VSS49_AA3") (pintype "power_in"))
      (node (ref "U1") (pin "AA7") (pinfunction "VSS50_AA7") (pintype "power_in"))
      (node (ref "U1") (pin "AB10") (pinfunction "VSS51_AB10") (pintype "power_in"))
      (node (ref "U1") (pin "AB12") (pinfunction "VSS52_AB12") (pintype "power_in"))
      (node (ref "U1") (pin "AB14") (pinfunction "VSS53_AB14") (pintype "power_in"))
      (node (ref "U1") (pin "AB16") (pinfunction "VSS54_AB16") (pintype "power_in"))
      (node (ref "U1") (pin "AB18") (pinfunction "VSS56_AB18") (pintype "power_in"))
      (node (ref "U1") (pin "AB20") (pinfunction "VSS57_AB20") (pintype "power_in"))
      (node (ref "U1") (pin "AB22") (pinfunction "VSS58_AB22") (pintype "power_in"))
      (node (ref "U1") (pin "AB8") (pinfunction "VSS59_AB8") (pintype "power_in"))
      (node (ref "U1") (pin "AC24") (pinfunction "VSS60_AC24") (pintype "power_in"))
      (node (ref "U1") (pin "AC27") (pinfunction "VSS61_AC27") (pintype "power_in"))
      (node (ref "U1") (pin "AC3") (pinfunction "VSS62_AC3") (pintype "power_in"))
      (node (ref "U1") (pin "AC6") (pinfunction "VSS63_AC6") (pintype "power_in"))
      (node (ref "U1") (pin "AE27") (pinfunction "VSS64_AE27") (pintype "power_in"))
      (node (ref "U1") (pin "AE3") (pinfunction "VSS65_AE3") (pintype "power_in"))
      (node (ref "U1") (pin "AG10") (pinfunction "VSS67_AG10") (pintype "power_in"))
      (node (ref "U1") (pin "AG12") (pinfunction "VSS68_AG12") (pintype "power_in"))
      (node (ref "U1") (pin "AG14") (pinfunction "VSS69_AG14") (pintype "power_in"))
      (node (ref "U1") (pin "AG16") (pinfunction "VSS70_AG16") (pintype "power_in"))
      (node (ref "U1") (pin "AG18") (pinfunction "VSS71_AG18") (pintype "power_in"))
      (node (ref "U1") (pin "AG20") (pinfunction "VSS72_AG20") (pintype "power_in"))
      (node (ref "U1") (pin "AG22") (pinfunction "VSS73_AG22") (pintype "power_in"))
      (node (ref "U1") (pin "AG24") (pinfunction "VSS74_AG24") (pintype "power_in"))
      (node (ref "U1") (pin "AG26") (pinfunction "VSS75_AG26") (pintype "power_in"))
      (node (ref "U1") (pin "AG4") (pinfunction "VSS76_AG4") (pintype "power_in"))
      (node (ref "U1") (pin "AG6") (pinfunction "VSS78_AG6") (pintype "power_in"))
      (node (ref "U1") (pin "AG8") (pinfunction "VSS79_AG8") (pintype "power_in"))
      (node (ref "U1") (pin "AJ1") (pinfunction "VSS80_AJ1") (pintype "power_in"))
      (node (ref "U1") (pin "AJ29") (pinfunction "VSS81_AJ29") (pintype "power_in"))
      (node (ref "U1") (pin "C10") (pinfunction "VSS82_C10") (pintype "power_in"))
      (node (ref "U1") (pin "C12") (pinfunction "VSS83_C12") (pintype "power_in"))
      (node (ref "U1") (pin "C14") (pinfunction "VSS84_C14") (pintype "power_in"))
      (node (ref "U1") (pin "C16") (pinfunction "VSS85_C16") (pintype "power_in"))
      (node (ref "U1") (pin "C18") (pinfunction "VSS86_C18") (pintype "power_in"))
      (node (ref "U1") (pin "C20") (pinfunction "VSS87_C20") (pintype "power_in"))
      (node (ref "U1") (pin "C22") (pinfunction "VSS89_C22") (pintype "power_in"))
      (node (ref "U1") (pin "C24") (pinfunction "VSS90_C24") (pintype "power_in"))
      (node (ref "U1") (pin "C26") (pinfunction "VSS91_C26") (pintype "power_in"))
      (node (ref "U1") (pin "C4") (pinfunction "VSS92_C4") (pintype "power_in"))
      (node (ref "U1") (pin "C6") (pinfunction "VSS93_C6") (pintype "power_in"))
      (node (ref "U1") (pin "C8") (pinfunction "VSS94_C8") (pintype "power_in"))
      (node (ref "U1") (pin "E27") (pinfunction "VSS95_E27") (pintype "power_in"))
      (node (ref "U1") (pin "E3") (pinfunction "VSS96_E3") (pintype "power_in"))
      (node (ref "U1") (pin "G24") (pinfunction "VSS97_G24") (pintype "power_in"))
      (node (ref "U1") (pin "G27") (pinfunction "VSS10_G27") (pintype "power_in"))
      (node (ref "U1") (pin "G3") (pinfunction "VSS11_G3") (pintype "power_in"))
      (node (ref "U1") (pin "G6") (pinfunction "VSS98_G6") (pintype "power_in"))
      (node (ref "U1") (pin "H10") (pinfunction "VSS100_H10") (pintype "power_in"))
      (node (ref "U1") (pin "H12") (pinfunction "VSS101_H12") (pintype "power_in"))
      (node (ref "U1") (pin "H14") (pinfunction "VSS102_H14") (pintype "power_in"))
      (node (ref "U1") (pin "H16") (pinfunction "VSS103_H16") (pintype "power_in"))
      (node (ref "U1") (pin "H18") (pinfunction "VSS104_H18") (pintype "power_in"))
      (node (ref "U1") (pin "H20") (pinfunction "VSS105_H20") (pintype "power_in"))
      (node (ref "U1") (pin "H22") (pinfunction "VSS106_H22") (pintype "power_in"))
      (node (ref "U1") (pin "H8") (pinfunction "VSS107_H8") (pintype "power_in"))
      (node (ref "U1") (pin "J23") (pinfunction "VSS108_J23") (pintype "power_in"))
      (node (ref "U1") (pin "J27") (pinfunction "VSS109_J27") (pintype "power_in"))
      (node (ref "U1") (pin "J3") (pinfunction "VSS3_J3") (pintype "power_in"))
      (node (ref "U1") (pin "J7") (pinfunction "VSS4_J7") (pintype "power_in"))
      (node (ref "U1") (pin "L14") (pinfunction "VSS5_L14") (pintype "power_in"))
      (node (ref "U1") (pin "L16") (pinfunction "VSS6_L16") (pintype "power_in"))
      (node (ref "U1") (pin "L23") (pinfunction "VSS7_L23") (pintype "power_in"))
      (node (ref "U1") (pin "L27") (pinfunction "VSS8_L27") (pintype "power_in"))
      (node (ref "U1") (pin "L3") (pinfunction "VSS9_L3") (pintype "power_in"))
      (node (ref "U1") (pin "L7") (pinfunction "VSS1_L7") (pintype "power_in"))
      (node (ref "U1") (pin "M11") (pinfunction "VSS22_M11") (pintype "power_in"))
      (node (ref "U1") (pin "M19") (pinfunction "VSS33_M19") (pintype "power_in"))
      (node (ref "U1") (pin "N11") (pinfunction "VSS44_N11") (pintype "power_in"))
      (node (ref "U1") (pin "N19") (pinfunction "VSS55_N19") (pintype "power_in"))
      (node (ref "U1") (pin "N23") (pinfunction "VSS66_N23") (pintype "power_in"))
      (node (ref "U1") (pin "N27") (pinfunction "VSS77_N27") (pintype "power_in"))
      (node (ref "U1") (pin "N3") (pinfunction "VSS88_N3") (pintype "power_in"))
      (node (ref "U1") (pin "N7") (pinfunction "VSS99_N7") (pintype "power_in"))
      (node (ref "U1") (pin "P11") (pinfunction "VSS2_P11") (pintype "power_in"))
      (node (ref "U1") (pin "P19") (pinfunction "VSS13_P19") (pintype "power_in"))
      (node (ref "U1") (pin "R11") (pinfunction "VSS14_R11") (pintype "power_in"))
      (node (ref "U1") (pin "R12") (pinfunction "VSS15_R12") (pintype "power_in"))
      (node (ref "U1") (pin "R13") (pinfunction "VSS16_R13") (pintype "power_in"))
      (node (ref "U1") (pin "R14") (pinfunction "VSS17_R14") (pintype "power_in"))
      (node (ref "U1") (pin "R16") (pinfunction "VSS18_R16") (pintype "power_in"))
      (node (ref "U1") (pin "R17") (pinfunction "VSS19_R17") (pintype "power_in"))
      (node (ref "U1") (pin "R18") (pinfunction "VSS20_R18") (pintype "power_in"))
      (node (ref "U1") (pin "R19") (pinfunction "VSS21_R19") (pintype "power_in"))
      (node (ref "U1") (pin "R23") (pinfunction "VSS23_R23") (pintype "power_in"))
      (node (ref "U1") (pin "R27") (pinfunction "VSS24_R27") (pintype "power_in"))
      (node (ref "U1") (pin "R3") (pinfunction "VSS25_R3") (pintype "power_in"))
      (node (ref "U1") (pin "R7") (pinfunction "VSS26_R7") (pintype "power_in"))
      (node (ref "U1") (pin "T11") (pinfunction "VSS27_T11") (pintype "power_in"))
      (node (ref "U1") (pin "T19") (pinfunction "VSS28_T19") (pintype "power_in"))
      (node (ref "U1") (pin "U11") (pinfunction "VSS29_U11") (pintype "power_in"))
      (node (ref "U1") (pin "U18") (pinfunction "VSS30_U18") (pintype "power_in"))
      (node (ref "U1") (pin "U19") (pinfunction "VSS31_U19") (pintype "power_in"))
      (node (ref "U1") (pin "U23") (pinfunction "VSS32_U23") (pintype "power_in"))
      (node (ref "U1") (pin "U27") (pinfunction "VSS34_U27") (pintype "power_in"))
      (node (ref "U1") (pin "U3") (pinfunction "VSS35_U3") (pintype "power_in"))
      (node (ref "U1") (pin "U7") (pinfunction "VSS36_U7") (pintype "power_in"))
      (node (ref "U1") (pin "V11") (pinfunction "VSS37_V11") (pintype "power_in"))
      (node (ref "U1") (pin "V19") (pinfunction "VSS38_V19") (pintype "power_in"))
      (node (ref "U1") (pin "W14") (pinfunction "VSS39_W14") (pintype "power_in"))
      (node (ref "U1") (pin "W16") (pinfunction "VSS40_W16") (pintype "power_in"))
      (node (ref "U1") (pin "W23") (pinfunction "VSS41_W23") (pintype "power_in"))
      (node (ref "U1") (pin "W27") (pinfunction "VSS42_W27") (pintype "power_in"))
      (node (ref "U1") (pin "W3") (pinfunction "VSS43_W3") (pintype "power_in"))
      (node (ref "U1") (pin "W7") (pinfunction "VSS45_W7") (pintype "power_in"))
    )
    (net (code "3") (name "NVCC_DRAM_1V1") (class "Default")
      (node (ref "C54") (pin "2") (pinfunction "2_2") (pintype "passive"))
      (node (ref "C55") (pin "2") (pinfunction "2_2") (pintype "passive"))
      (node (ref "C56") (pin "2") (pinfunction "2_2") (pintype "passive"))
      (node (ref "C57") (pin "2") (pinfunction "2_2") (pintype "passive"))
      (node (ref "C58") (pin "2") (pinfunction "2_2") (pintype "passive"))
      (node (ref "C59") (pin "2") (pinfunction "2_2") (pintype "passive"))
      (node (ref "C60") (pin "2") (pinfunction "2_2") (pintype "passive"))
      (node (ref "C61") (pin "2") (pinfunction "2_2") (pintype "passive"))
      (node (ref "C62") (pin "2") (pinfunction "2_2") (pintype "passive"))
      (node (ref "U1") (pin "AA10") (pinfunction "NVCC_DRAM_1_AA10") (pintype "power_in"))
      (node (ref "U1") (pin "AA8") (pinfunction "NVCC_DRAM_2_AA8") (pintype "power_in"))
      (node (ref "U1") (pin "J10") (pinfunction "NVCC_DRAM_3_J10") (pintype "power_in"))
      (node (ref "U1") (pin "J8") (pinfunction "NVCC_DRAM_4_J8") (pintype "power_in"))
      (node (ref "U1") (pin "L8") (pinfunction "NVCC_DRAM_5_L8") (pintype "power_in"))
      (node (ref "U1") (pin "N8") (pinfunction "NVCC_DRAM_6_N8") (pintype "power_in"))
      (node (ref "U1") (pin "R8") (pinfunction "NVCC_DRAM_7_R8") (pintype "power_in"))
      (node (ref "U1") (pin "U8") (pinfunction "NVCC_DRAM_8_U8") (pintype "power_in"))
      (node (ref "U1") (pin "W8") (pinfunction "NVCC_DRAM_9_W8") (pintype "power_in"))
    )
    (net (code "4") (name "NVCC_SD2") (class "Default")
      (node (ref "C17") (pin "2") (pinfunction "2_2") (pintype "passive"))
      (node (ref "U1") (pin "W24") (pinfunction "NVCC_SD2_W24") (pintype "power_in"))
    )
    (net (code "5") (name "NVCC_SNVS_1V8") (class "Default")
      (node (ref "C5") (pin "2") (pinfunction "2_2") (pintype "passive"))
      (node (ref "U1") (pin "R24") (pinfunction "NVCC_SNVS_1P8_R24") (pintype "power_in"))
    )
    (net (code "6") (name "VDDA_1V8") (class "Default")
      (node (ref "C33") (pin "2") (pinfunction "2_2") (pintype "passive"))
      (node (ref "C34") (pin "2") (pinfunction "2_2") (pintype "passive"))
      (node (ref "C35") (pin "2") (pinfunction "2_2") (pintype "passive"))
      (node (ref "C36") (pin "2") (pinfunction "2_2") (pintype "passive"))
      (node (ref "C37") (pin "2") (pinfunction "2_2") (pintype "passive"))
      (node (ref "C42") (pin "2") (pinfunction "2_2") (pintype "passive"))
      (node (ref "C43") (pin "2") (pinfunction "2_2") (pintype "passive"))
      (node (ref "C44") (pin "2") (pinfunction "2_2") (pintype "passive"))
      (node (ref "C45") (pin "2") (pinfunction "2_2") (pintype "passive"))
      (node (ref "C7") (pin "2") (pinfunction "2_2") (pintype "passive"))
      (node (ref "U1") (pin "AA20") (pinfunction "VDD_EARC_1P8_AA20") (pintype "power_in"))
      (node (ref "U1") (pin "AA22") (pinfunction "VDD_HDMI_1P8_AA22") (pintype "power_in"))
      (node (ref "U1") (pin "J19") (pinfunction "VDD_USB_1P8_J19") (pintype "passive"))
      (node (ref "U1") (pin "J20") (pinfunction "VDD_ANA0_1P8_J20") (pintype "power_in"))
      (node (ref "U1") (pin "J22") (pinfunction "VDD_LVDS_1P8_J22") (pintype "power_in"))
      (node (ref "U1") (pin "K19") (pinfunction "VDD_PCI_1P8_K19") (pintype "power_in"))
      (node (ref "U1") (pin "K20") (pinfunction "VDD_MIPI_1P8_K20") (pintype "power_in"))
      (node (ref "U1") (pin "L22") (pinfunction "VDD_24M_XTAL_1P8_L22") (pintype "power_in"))
      (node (ref "U1") (pin "N22") (pinfunction "VDD_ANA1_1P8_N22") (pintype "power_in"))
      (node (ref "U1") (pin "R6") (pinfunction "VDD_DRAM_PLL_1P8_R6") (pintype "power_in"))
      (node (ref "U1") (pin "W18") (pinfunction "VDD_SAI_PLL_1P8_W18") (pintype "power_in"))
      (node (ref "U1") (pin "W19") (pinfunction "VDD_AVPLL_1P8_W19") (pintype "power_in"))
      (node (ref "U1") (pin "Y19") (pinfunction "VDD_ARM_PLL_1P8_Y19") (pintype "power_in"))
      (node (ref "U1") (pin "Y20") (pinfunction "VDD_ANA2_1P8_Y20") (pintype "power_in"))
    )
    (net (code "7") (name "VDD_1V8") (class "Default")
      (node (ref "C1") (pin "2") (pinfunction "2_2") (pintype "passive"))
      (node (ref "C10") (pin "2") (pinfunction "2_2") (pintype "passive"))
      (node (ref "C16") (pin "2") (pinfunction "2_2") (pintype "passive"))
      (node (ref "C2") (pin "2") (pinfunction "2_2") (pintype "passive"))
      (node (ref "C24") (pin "2") (pinfunction "2_2") (pintype "passive"))
      (node (ref "C3") (pin "2") (pinfunction "2_2") (pintype "passive"))
      (node (ref "C4") (pin "2") (pinfunction "2_2") (pintype "passive"))
      (node (ref "C8") (pin "2") (pinfunction "2_2") (pintype "passive"))
      (node (ref "C9") (pin "2") (pinfunction "2_2") (pintype "passive"))
      (node (ref "U1") (pin "AA11") (pinfunction "NVCC_SAI2_SAI3_SPDIF_AA11") (pintype "power_in"))
      (node (ref "U1") (pin "AA14") (pinfunction "NVCC_ECSPI_HDMI_AA14") (pintype "power_in"))
      (node (ref "U1") (pin "AA16") (pinfunction "PVCC2_1P8_AA16") (pintype "power_in"))
      (node (ref "U1") (pin "AA19") (pinfunction "PVCC1_1P8_AA19") (pintype "power_in"))
      (node (ref "U1") (pin "AA24") (pinfunction "NVCC_ENET_AA24") (pintype "power_in"))
      (node (ref "U1") (pin "J11") (pinfunction "NVCC_GPIO_J11") (pintype "power_in"))
      (node (ref "U1") (pin "J16") (pinfunction "PVCC0_1P8_J16") (pintype "power_in"))
      (node (ref "U1") (pin "K11") (pinfunction "NVCC_JTAG_K11") (pintype "power_in"))
      (node (ref "U1") (pin "R22") (pinfunction "NVCC_CLK_R22") (pintype "power_in"))
      (node (ref "U1") (pin "U22") (pinfunction "NVCC_NAND_U22") (pintype "power_in"))
      (node (ref "U1") (pin "U24") (pinfunction "NVCC_SD1_U24") (pintype "power_in"))
      (node (ref "U1") (pin "Y10") (pinfunction "NVCC_I2C_UART_Y10") (pintype "power_in"))
      (node (ref "U1") (pin "Y11") (pinfunction "NVCC_SAI1_SAI5_Y11") (pintype "power_in"))
    )
    (net (code "8") (name "VDD_3V3") (class "Default")
      (node (ref "C18") (pin "2") (pinfunction "2_2") (pintype "passive"))
      (node (ref "U1") (pin "J14") (pinfunction "VDD_USB_3P3_J14") (pintype "passive"))
    )
    (net (code "9") (name "VDD_ARM") (class "Default")
      (node (ref "C11") (pin "2") (pinfunction "2_2") (pintype "passive"))
      (node (ref "C12") (pin "2") (pinfunction "2_2") (pintype "passive"))
      (node (ref "C13") (pin "2") (pinfunction "2_2") (pintype "passive"))
      (node (ref "C14") (pin "2") (pinfunction "2_2") (pintype "passive"))
      (node (ref "C15") (pin "2") (pinfunction "2_2") (pintype "passive"))
      (node (ref "C19") (pin "2") (pinfunction "2_2") (pintype "passive"))
      (node (ref "C20") (pin "2") (pinfunction "2_2") (pintype "passive"))
      (node (ref "C21") (pin "2") (pinfunction "2_2") (pintype "passive"))
      (node (ref "C22") (pin "2") (pinfunction "2_2") (pintype "passive"))
      (node (ref "C23") (pin "2") (pinfunction "2_2") (pintype "passive"))
      (node (ref "U1") (pin "T14") (pinfunction "VDD_ARM_1_T14") (pintype "power_in"))
      (node (ref "U1") (pin "T16") (pinfunction "VDD_ARM_2_T16") (pintype "power_in"))
      (node (ref "U1") (pin "U12") (pinfunction "VDD_ARM_3_U12") (pintype "power_in"))
      (node (ref "U1") (pin "U13") (pinfunction "VDD_ARM_4_U13") (pintype "power_in"))
      (node (ref "U1") (pin "U14") (pinfunction "VDD_ARM_5_U14") (pintype "power_in"))
      (node (ref "U1") (pin "U15") (pinfunction "VDD_ARM_6_U15") (pintype "power_in"))
      (node (ref "U1") (pin "U16") (pinfunction "VDD_ARM_7_U16") (pintype "power_in"))
      (node (ref "U1") (pin "U17") (pinfunction "VDD_ARM_8_U17") (pintype "power_in"))
      (node (ref "U1") (pin "V14") (pinfunction "VDD_ARM_9_V14") (pintype "power_in"))
      (node (ref "U1") (pin "V16") (pinfunction "VDD_ARM_10_V16") (pintype "power_in"))
      (node (ref "U1") (pin "W12") (pinfunction "VDD_ARM_11_W12") (pintype "power_in"))
      (node (ref "U1") (pin "W13") (pinfunction "VDD_ARM_12_W13") (pintype "power_in"))
      (node (ref "U1") (pin "W17") (pinfunction "VDD_ARM_13_W17") (pintype "power_in"))
      (node (ref "U1") (pin "Y14") (pinfunction "VDD_ARM_14_Y14") (pintype "power_in"))
      (node (ref "U1") (pin "Y15") (pinfunction "VDD_ARM_15_Y15") (pintype "power_in"))
      (node (ref "U1") (pin "Y16") (pinfunction "VDD_ARM_16_Y16") (pintype "power_in"))
    )
    (net (code "10") (name "VDD_SNVS_0V8") (class "Default")
      (node (ref "C6") (pin "2") (pinfunction "2_2") (pintype "passive"))
      (node (ref "U1") (pin "N26") (pinfunction "VDD_SNVS_0P8_CAP_N26") (pintype "power_in"))
    )
    (net (code "11") (name "VDD_SOC") (class "Default")
      (node (ref "C25") (pin "2") (pinfunction "2_2") (pintype "passive"))
      (node (ref "C26") (pin "2") (pinfunction "2_2") (pintype "passive"))
      (node (ref "C27") (pin "2") (pinfunction "2_2") (pintype "passive"))
      (node (ref "C28") (pin "2") (pinfunction "2_2") (pintype "passive"))
      (node (ref "C29") (pin "2") (pinfunction "2_2") (pintype "passive"))
      (node (ref "C30") (pin "2") (pinfunction "2_2") (pintype "passive"))
      (node (ref "C31") (pin "2") (pinfunction "2_2") (pintype "passive"))
      (node (ref "C32") (pin "2") (pinfunction "2_2") (pintype "passive"))
      (node (ref "C38") (pin "2") (pinfunction "2_2") (pintype "passive"))
      (node (ref "C39") (pin "2") (pinfunction "2_2") (pintype "passive"))
      (node (ref "C40") (pin "2") (pinfunction "2_2") (pintype "passive"))
      (node (ref "C41") (pin "2") (pinfunction "2_2") (pintype "passive"))
      (node (ref "C46") (pin "2") (pinfunction "2_2") (pintype "passive"))
      (node (ref "C47") (pin "2") (pinfunction "2_2") (pintype "passive"))
      (node (ref "C48") (pin "2") (pinfunction "2_2") (pintype "passive"))
      (node (ref "C49") (pin "2") (pinfunction "2_2") (pintype "passive"))
      (node (ref "C50") (pin "2") (pinfunction "2_2") (pintype "passive"))
      (node (ref "C51") (pin "2") (pinfunction "2_2") (pintype "passive"))
      (node (ref "C52") (pin "2") (pinfunction "2_2") (pintype "passive"))
      (node (ref "C53") (pin "2") (pinfunction "2_2") (pintype "passive"))
      (node (ref "TP1") (pin "1") (pinfunction "1_1") (pintype "passive"))
      (node (ref "U1") (pin "K10") (pinfunction "VDD_SOC_1_K10") (pintype "power_in"))
      (node (ref "U1") (pin "K14") (pinfunction "VDD_USB_0P8_K14") (pintype "passive"))
      (node (ref "U1") (pin "K15") (pinfunction "VDD_PCI_0P8_K15") (pintype "power_in"))
      (node (ref "U1") (pin "K16") (pinfunction "VDD_MIPI_0P8_K16") (pintype "power_in"))
      (node (ref "U1") (pin "L10") (pinfunction "VDD_SOC_2_L10") (pintype "power_in"))
      (node (ref "U1") (pin "L11") (pinfunction "VDD_SOC_3_L11") (pintype "power_in"))
      (node (ref "U1") (pin "L12") (pinfunction "VDD_SOC_4_L12") (pintype "power_in"))
      (node (ref "U1") (pin "L13") (pinfunction "VDD_SOC_5_L13") (pintype "power_in"))
      (node (ref "U1") (pin "L17") (pinfunction "VDD_SOC_6_L17") (pintype "power_in"))
      (node (ref "U1") (pin "L18") (pinfunction "VDD_SOC_7_L18") (pintype "power_in"))
      (node (ref "U1") (pin "L19") (pinfunction "VDD_SOC_8_L19") (pintype "power_in"))
      (node (ref "U1") (pin "L20") (pinfunction "VDD_SOC_9_L20") (pintype "power_in"))
      (node (ref "U1") (pin "L21") (pinfunction "VDD_SOC_10_L21") (pintype "power_in"))
      (node (ref "U1") (pin "L9") (pinfunction "VDD_SOC_11_L9") (pintype "power_in"))
      (node (ref "U1") (pin "M14") (pinfunction "VDD_SOC_12_M14") (pintype "power_in"))
      (node (ref "U1") (pin "M16") (pinfunction "VDD_SOC_13_M16") (pintype "power_in"))
      (node (ref "U1") (pin "N10") (pinfunction "VDD_SOC_14_N10") (pintype "power_in"))
      (node (ref "U1") (pin "N12") (pinfunction "VDD_SOC_15_N12") (pintype "power_in"))
      (node (ref "U1") (pin "N13") (pinfunction "VDD_SOC_16_N13") (pintype "power_in"))
      (node (ref "U1") (pin "N14") (pinfunction "VDD_SOC_34_N14") (pintype "power_in"))
      (node (ref "U1") (pin "N15") (pinfunction "VDD_SOC_33_N15") (pintype "power_in"))
      (node (ref "U1") (pin "N16") (pinfunction "VDD_SOC_32_N16") (pintype "power_in"))
      (node (ref "U1") (pin "N17") (pinfunction "VDD_SOC_31_N17") (pintype "power_in"))
      (node (ref "U1") (pin "N18") (pinfunction "VDD_SOC_30_N18") (pintype "power_in"))
      (node (ref "U1") (pin "N20") (pinfunction "VDD_SOC_29_N20") (pintype "power_in"))
      (node (ref "U1") (pin "N21") (pinfunction "VDD_SOC_35_N21") (pintype "power_in"))
      (node (ref "U1") (pin "N9") (pinfunction "VDD_SOC_28_N9") (pintype "power_in"))
      (node (ref "U1") (pin "P14") (pinfunction "VDD_SOC_27_P14") (pintype "power_in"))
      (node (ref "U1") (pin "P16") (pinfunction "VDD_SOC_26_P16") (pintype "power_in"))
      (node (ref "U1") (pin "R10") (pinfunction "VDD_SOC_25_R10") (pintype "power_in"))
      (node (ref "U1") (pin "R20") (pinfunction "VDD_SOC_24_R20") (pintype "power_in"))
      (node (ref "U1") (pin "R21") (pinfunction "VDD_ANA1_0P8_R21") (pintype "power_in"))
      (node (ref "U1") (pin "R9") (pinfunction "VDD_DRAM_PLL_0P8_R9") (pintype "power_in"))
      (node (ref "U1") (pin "U10") (pinfunction "VDD_SOC_23_U10") (pintype "power_in"))
      (node (ref "U1") (pin "U20") (pinfunction "VDD_SOC_22_U20") (pintype "power_in"))
      (node (ref "U1") (pin "U21") (pinfunction "VDD_SAI_PLL_0P8_U21") (pintype "power_in"))
      (node (ref "U1") (pin "U9") (pinfunction "VDD_SOC_20_U9") (pintype "power_in"))
      (node (ref "U1") (pin "W10") (pinfunction "VDD_SOC_19_W10") (pintype "power_in"))
      (node (ref "U1") (pin "W11") (pinfunction "VDD_SOC_18_W11") (pintype "power_in"))
      (node (ref "U1") (pin "W20") (pinfunction "VDD_SOC_21_W20") (pintype "power_in"))
      (node (ref "U1") (pin "W21") (pinfunction "VDD_ARM_PLL_0P8_W21") (pintype "power_in"))
      (node (ref "U1") (pin "W22") (pinfunction "VDD_HDMI_0P8_W22") (pintype "power_in"))
      (node (ref "U1") (pin "W9") (pinfunction "VDD_SOC_17_W9") (pintype "power_in"))
    )
  )
)
